# H14R90.net
KiCad netlist of a schematic drawn in EAGLE
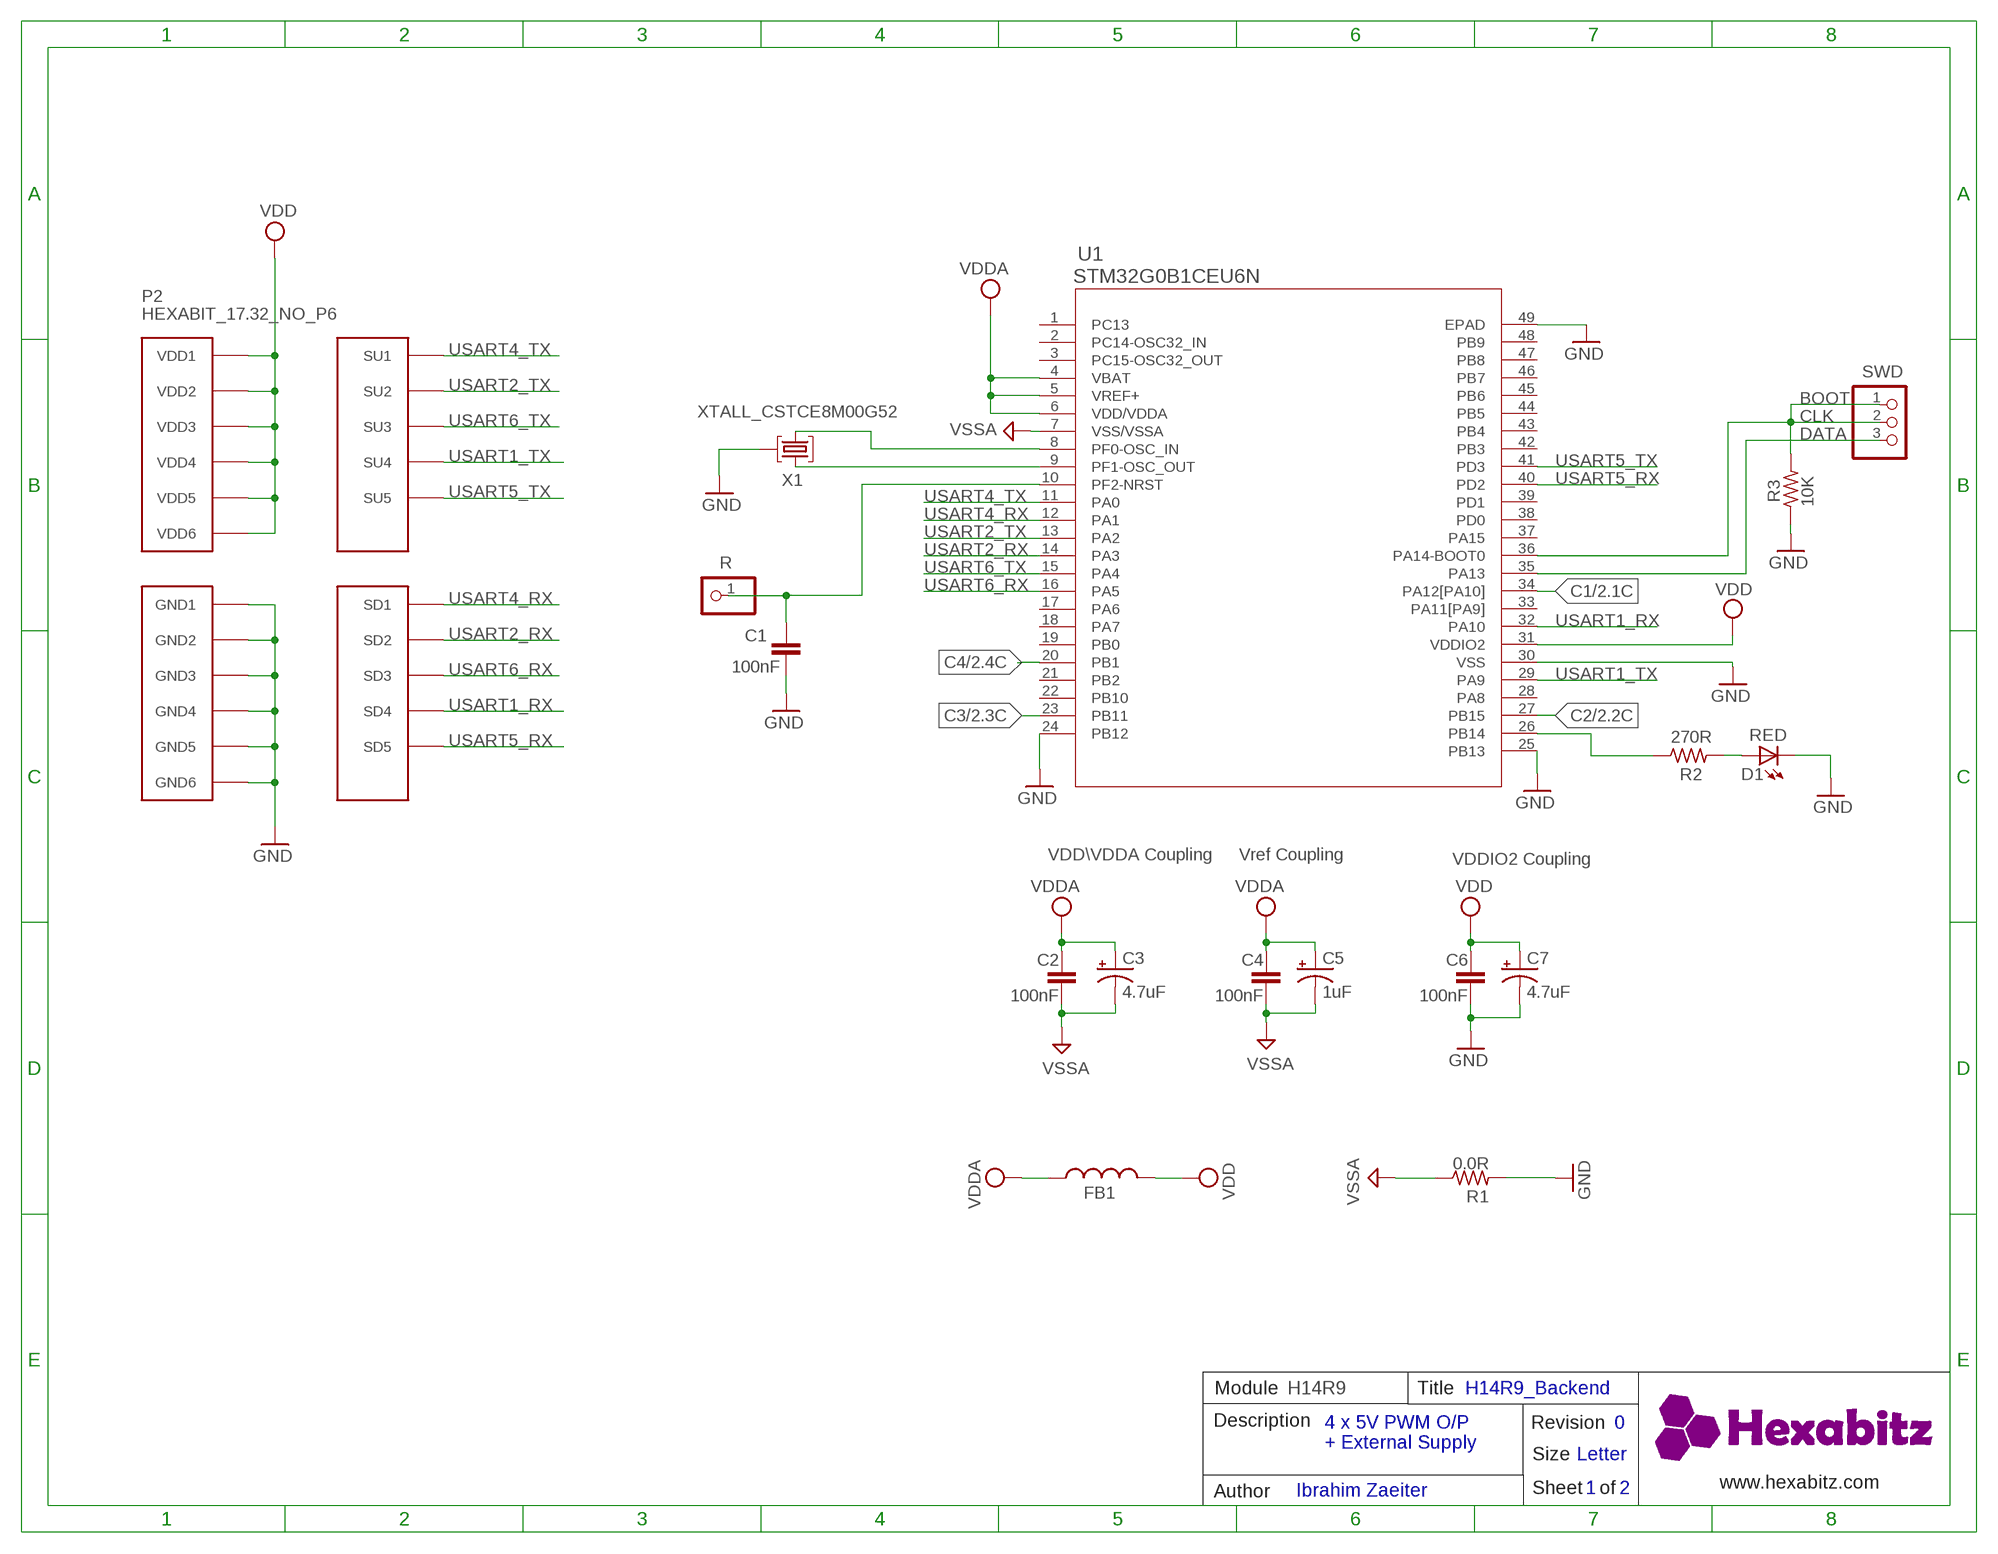
[diagram p0: schematic, sheet 1]
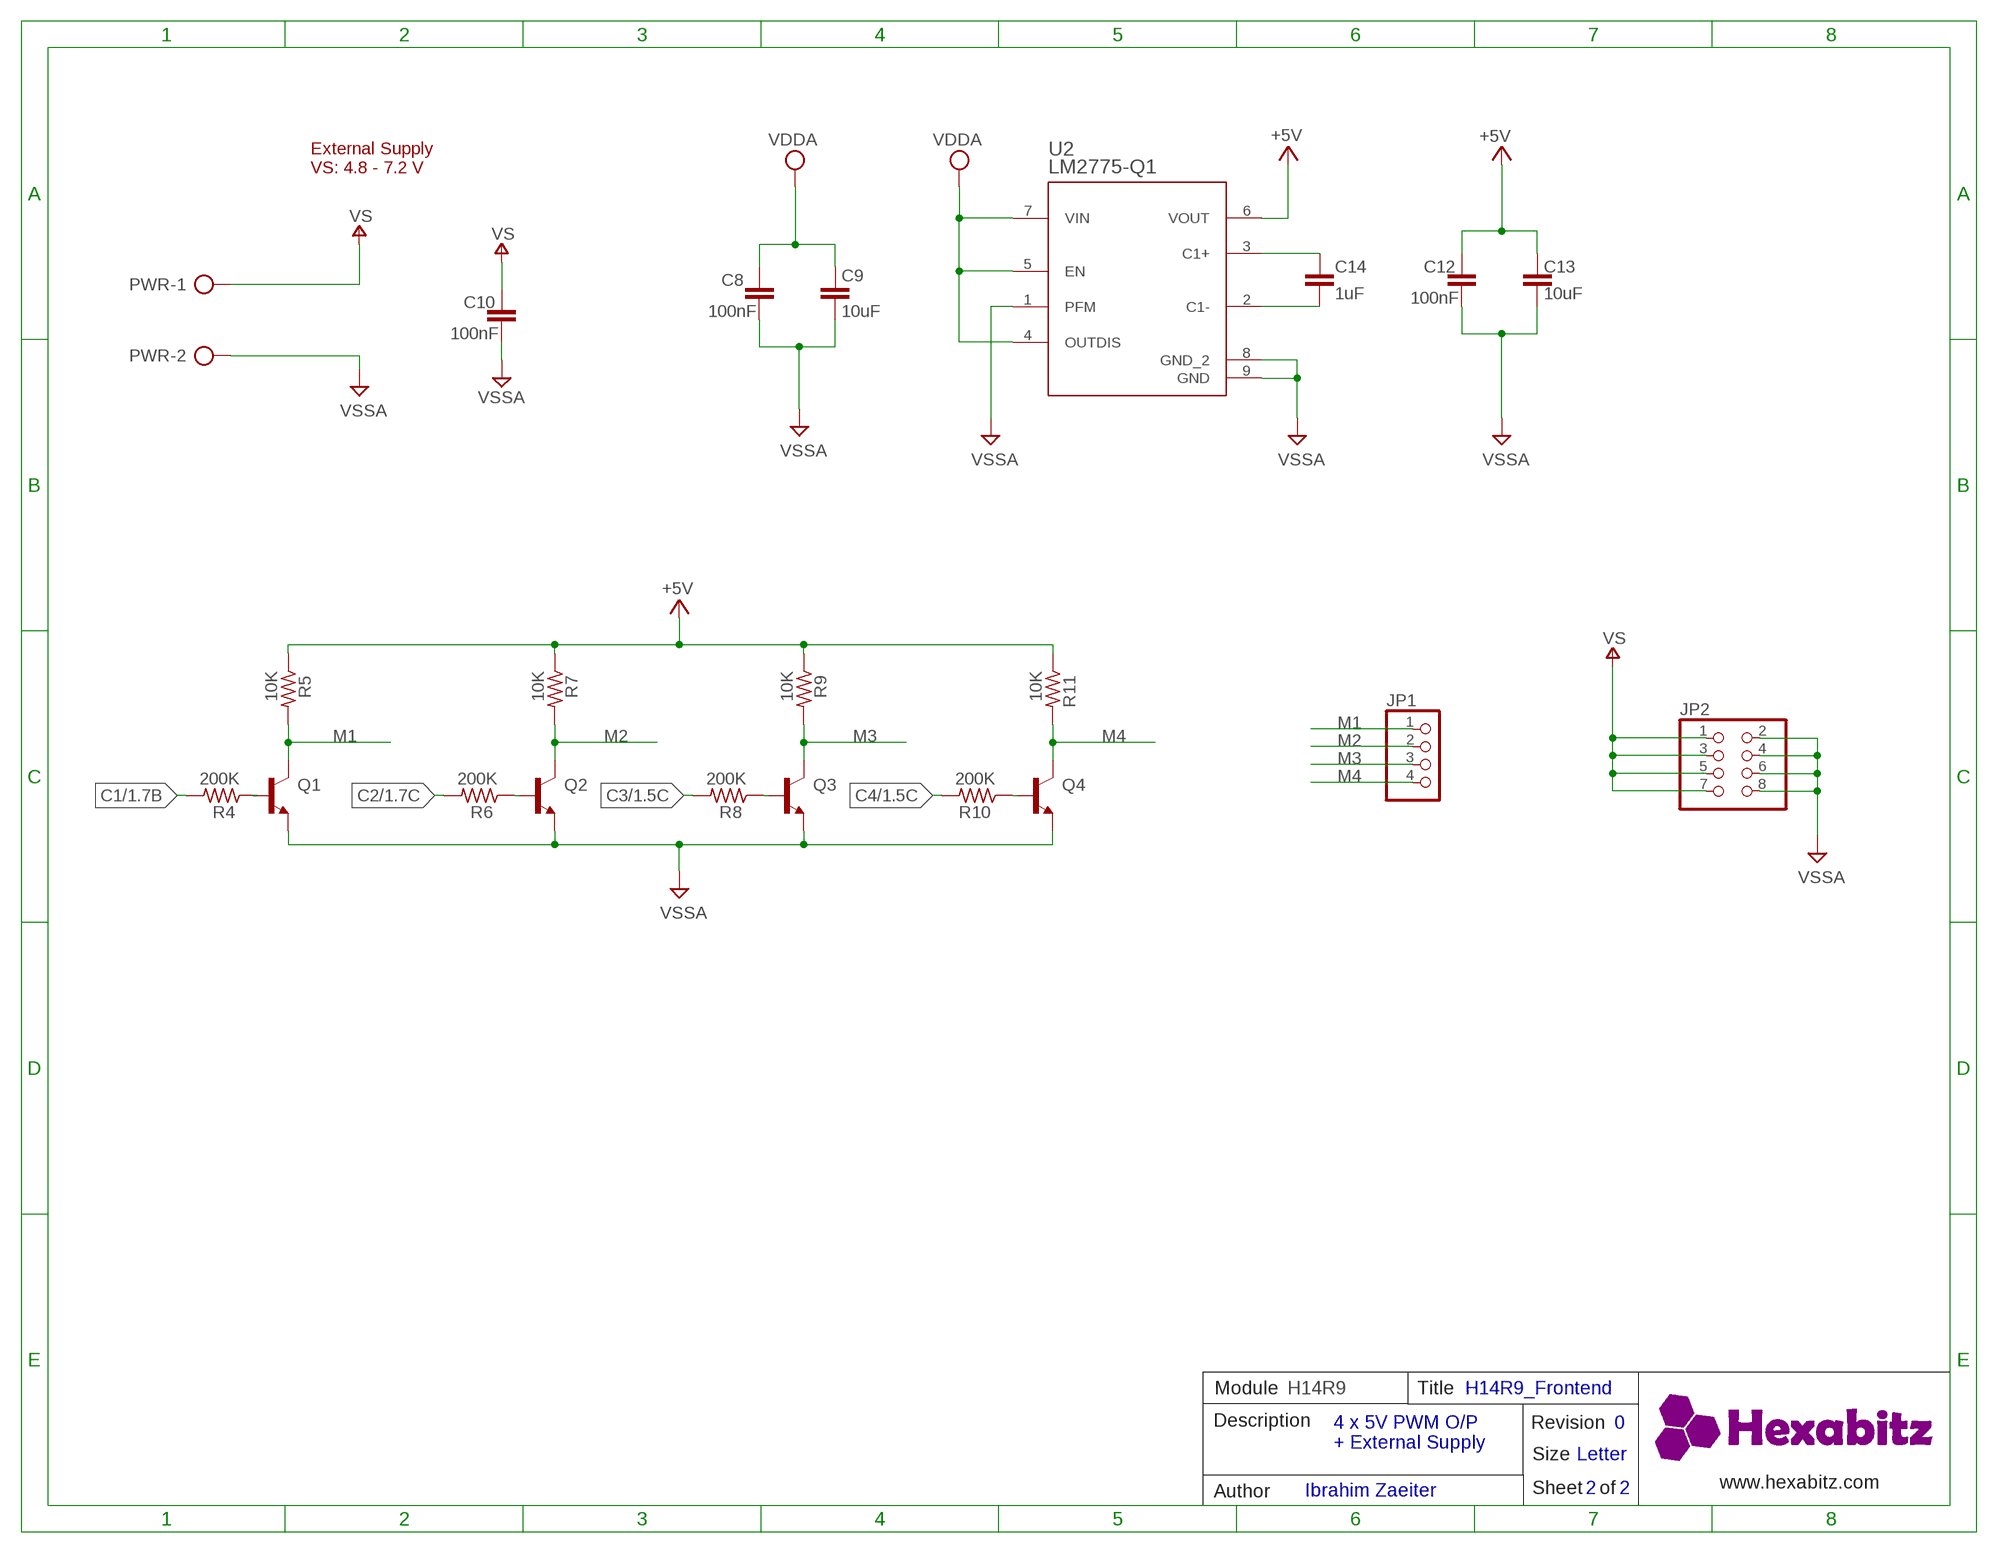
[diagram p1: schematic, sheet 2]

(export (version "E")
  (design (tool "Eeschema 10.0.6"))
  (components
    (comp (ref "C8")
      (value "100nF")
      (footprint "eagle-import:C-0603")
      (libsource (lib "eagle-import") (part "C-0603"))
    )
    (comp (ref "C9")
      (value "10uF")
      (footprint "eagle-import:C-0603")
      (libsource (lib "eagle-import") (part "C-0603"))
    )
    (comp (ref "C10")
      (value "100nF")
      (footprint "eagle-import:C-0603")
      (libsource (lib "eagle-import") (part "C-0603"))
    )
    (comp (ref "C12")
      (value "100nF")
      (footprint "eagle-import:C-0603")
      (libsource (lib "eagle-import") (part "C-0603"))
    )
    (comp (ref "C13")
      (value "10uF")
      (footprint "eagle-import:C-0603")
      (libsource (lib "eagle-import") (part "C-0603"))
    )
    (comp (ref "C14")
      (value "1uF")
      (footprint "eagle-import:C-0603")
      (libsource (lib "eagle-import") (part "C-0603"))
    )
    (comp (ref "JP1")
      (value "PINHD-1X4")
      (footprint "eagle-import:1X04")
      (libsource (lib "eagle-import") (part "PINHD-1X4"))
    )
    (comp (ref "JP2")
      (value "PINHD-2X4")
      (footprint "eagle-import:2X04")
      (libsource (lib "eagle-import") (part "PINHD-2X4"))
    )
    (comp (ref "PWR")
      (value "AK500/2")
      (footprint "eagle-import:AK500_2")
      (libsource (lib "eagle-import") (part "AK500/2"))
    )
    (comp (ref "Q1")
      (value "MMBT3904LT1")
      (footprint "eagle-import:MMBT3904LT1")
      (libsource (lib "eagle-import") (part "MMBT3904LT1"))
    )
    (comp (ref "Q2")
      (value "MMBT3904LT1")
      (footprint "eagle-import:MMBT3904LT1")
      (libsource (lib "eagle-import") (part "MMBT3904LT1"))
    )
    (comp (ref "Q3")
      (value "MMBT3904LT1")
      (footprint "eagle-import:MMBT3904LT1")
      (libsource (lib "eagle-import") (part "MMBT3904LT1"))
    )
    (comp (ref "Q4")
      (value "MMBT3904LT1")
      (footprint "eagle-import:MMBT3904LT1")
      (libsource (lib "eagle-import") (part "MMBT3904LT1"))
    )
    (comp (ref "R4")
      (value "200K")
      (footprint "eagle-import:R-0603")
      (libsource (lib "eagle-import") (part "R-0603"))
    )
    (comp (ref "R5")
      (value "10K")
      (footprint "eagle-import:R-0603")
      (libsource (lib "eagle-import") (part "R-0603"))
    )
    (comp (ref "R6")
      (value "200K")
      (footprint "eagle-import:R-0603")
      (libsource (lib "eagle-import") (part "R-0603"))
    )
    (comp (ref "R7")
      (value "10K")
      (footprint "eagle-import:R-0603")
      (libsource (lib "eagle-import") (part "R-0603"))
    )
    (comp (ref "R8")
      (value "200K")
      (footprint "eagle-import:R-0603")
      (libsource (lib "eagle-import") (part "R-0603"))
    )
    (comp (ref "R9")
      (value "10K")
      (footprint "eagle-import:R-0603")
      (libsource (lib "eagle-import") (part "R-0603"))
    )
    (comp (ref "R10")
      (value "200K")
      (footprint "eagle-import:R-0603")
      (libsource (lib "eagle-import") (part "R-0603"))
    )
    (comp (ref "R11")
      (value "10K")
      (footprint "eagle-import:R-0603")
      (libsource (lib "eagle-import") (part "R-0603"))
    )
    (comp (ref "U2")
      (value "LM2775-Q1")
      (footprint "eagle-import:DSG0008A")
      (fields (field (name "MANUFACTURER") "Texas Instruments") (field (name "MPN") "LM2775QDSGRQ1"))
      (libsource (lib "eagle-import") (part "LM2775QDSGRQ1"))
    )
    (comp (ref "C1")
      (value "100nF")
      (footprint "eagle-import:C-0603")
      (libsource (lib "eagle-import") (part "C-0603"))
    )
    (comp (ref "C2")
      (value "100nF")
      (footprint "eagle-import:C-0603")
      (libsource (lib "eagle-import") (part "C-0603"))
    )
    (comp (ref "C3")
      (value "4.7uF")
      (footprint "eagle-import:C-0805-POL")
      (libsource (lib "eagle-import") (part "C-0805-POL"))
    )
    (comp (ref "C4")
      (value "100nF")
      (footprint "eagle-import:C-0603")
      (libsource (lib "eagle-import") (part "C-0603"))
    )
    (comp (ref "C5")
      (value "1uF")
      (footprint "eagle-import:C-0805-POL")
      (libsource (lib "eagle-import") (part "C-0805-POL"))
    )
    (comp (ref "C6")
      (value "100nF")
      (footprint "eagle-import:C-0603")
      (libsource (lib "eagle-import") (part "C-0603"))
    )
    (comp (ref "C7")
      (value "4.7uF")
      (footprint "eagle-import:C-0805-POL")
      (libsource (lib "eagle-import") (part "C-0805-POL"))
    )
    (comp (ref "D1")
      (value "RED")
      (footprint "eagle-import:VLMS1300-GS08")
      (fields
        (field (name "MPN") "VLMS1300-GS08")
        (field (name "MFN") "Vishay")
        (field (name "MPN_1") "VLMS1300-GS08")
        (field (name "OCTOPART_URL") "https://octopart.com/vlms1300-gs08-vishay-21709201?r=sp&s=_gcP4_q8T1SC6PJQPTQ9yA")
      )
      (libsource (lib "eagle-import") (part "VLMS1300-GS08"))
    )
    (comp (ref "FB1")
      (value "FB-0603")
      (footprint "eagle-import:FB-0603")
      (libsource (lib "eagle-import") (part "FB-0603"))
    )
    (comp (ref "P2")
      (value "HEXABIT_17.32_NO_P6")
      (footprint "eagle-import:HEXABIT_17.32_NO_P6")
      (libsource (lib "eagle-import") (part "HEXABIT_?_NO_P617.32"))
    )
    (comp (ref "R")
      (value "R")
      (footprint "eagle-import:1X01")
      (fields (field (name "MPN") "87227-1"))
      (libsource (lib "eagle-import") (part "PINHD-1X1"))
    )
    (comp (ref "R1")
      (value "0.0R")
      (footprint "eagle-import:R-0603")
      (libsource (lib "eagle-import") (part "R-0603"))
    )
    (comp (ref "R2")
      (value "270R")
      (footprint "eagle-import:R-0603")
      (libsource (lib "eagle-import") (part "R-0603"))
    )
    (comp (ref "R3")
      (value "10K")
      (footprint "eagle-import:R-0603")
      (libsource (lib "eagle-import") (part "R-0603"))
    )
    (comp (ref "SWD")
      (value "PINHD-1X3")
      (footprint "eagle-import:1X03")
      (libsource (lib "eagle-import") (part "PINHD-1X3"))
    )
    (comp (ref "U1")
      (value "STM32G0B1CEU6N")
      (footprint "eagle-import:HEXABITZ_ICS_QFN_B1CEU6_STM-L")
      (libsource (lib "eagle-import") (part "STM32G0B1CEU6N"))
    )
    (comp (ref "X1")
      (value "XTALL_CSTCE8M00G52")
      (footprint "eagle-import:XTALL_CSTCE8M00G52")
      (fields (field (name "MPN") "CSTCE8M00G52Z-R0"))
      (libsource (lib "eagle-import") (part "XTALL_CSTCE8M00G52"))
    )
  )
  (nets
    (net (code "1") (name "+5V") (class "Default")
      (node (ref "C12") (pin "1") (pinfunction "1_1") (pintype "passive"))
      (node (ref "C13") (pin "1") (pinfunction "1_1") (pintype "passive"))
      (node (ref "R11") (pin "1") (pinfunction "1_1") (pintype "passive"))
      (node (ref "R5") (pin "1") (pinfunction "1_1") (pintype "passive"))
      (node (ref "R7") (pin "1") (pinfunction "1_1") (pintype "passive"))
      (node (ref "R9") (pin "1") (pinfunction "1_1") (pintype "passive"))
      (node (ref "U2") (pin "6") (pinfunction "VOUT_6") (pintype "power_in"))
    )
    (net (code "2") (name "C1") (class "Default")
      (node (ref "R4") (pin "2") (pinfunction "2_2") (pintype "passive"))
      (node (ref "U1") (pin "34") (pinfunction "PA12[PA10]_34") (pintype "bidirectional"))
    )
    (net (code "3") (name "C2") (class "Default")
      (node (ref "R6") (pin "2") (pinfunction "2_2") (pintype "passive"))
      (node (ref "U1") (pin "27") (pinfunction "PB15_27") (pintype "bidirectional"))
    )
    (net (code "4") (name "C3") (class "Default")
      (node (ref "R8") (pin "2") (pinfunction "2_2") (pintype "passive"))
      (node (ref "U1") (pin "23") (pinfunction "PB11_23") (pintype "bidirectional"))
    )
    (net (code "5") (name "C4") (class "Default")
      (node (ref "R10") (pin "2") (pinfunction "2_2") (pintype "passive"))
      (node (ref "U1") (pin "20") (pinfunction "PB1_20") (pintype "bidirectional"))
    )
    (net (code "6") (name "CLK") (class "Default")
      (node (ref "R3") (pin "2") (pinfunction "2_2") (pintype "passive"))
      (node (ref "SWD") (pin "1") (pinfunction "1_1") (pintype "passive"))
      (node (ref "SWD") (pin "2") (pinfunction "2_2") (pintype "passive"))
      (node (ref "U1") (pin "36") (pinfunction "PA14-BOOT0_36") (pintype "bidirectional"))
    )
    (net (code "7") (name "DATA") (class "Default")
      (node (ref "SWD") (pin "3") (pinfunction "3_3") (pintype "passive"))
      (node (ref "U1") (pin "35") (pinfunction "PA13_35") (pintype "bidirectional"))
    )
    (net (code "8") (name "GND") (class "Default")
      (node (ref "C1") (pin "2") (pinfunction "2_2") (pintype "passive"))
      (node (ref "C6") (pin "2") (pinfunction "2_2") (pintype "passive"))
      (node (ref "C7") (pin "2") (pinfunction "-_2") (pintype "passive"))
      (node (ref "D1") (pin "C") (pinfunction "C_C") (pintype "passive"))
      (node (ref "P2") (pin "PAD_PD10") (pinfunction "GND4_PAD_PD10") (pintype "power_in"))
      (node (ref "P2") (pin "PAD_PD11") (pinfunction "GND5_PAD_PD11") (pintype "power_in"))
      (node (ref "P2") (pin "PAD_PD12") (pinfunction "GND6_PAD_PD12") (pintype "power_in"))
      (node (ref "P2") (pin "PAD_PD7") (pinfunction "GND1_PAD_PD7") (pintype "power_in"))
      (node (ref "P2") (pin "PAD_PD8") (pinfunction "GND2_PAD_PD8") (pintype "power_in"))
      (node (ref "P2") (pin "PAD_PD9") (pinfunction "GND3_PAD_PD9") (pintype "power_in"))
      (node (ref "R1") (pin "2") (pinfunction "2_2") (pintype "passive"))
      (node (ref "R3") (pin "1") (pinfunction "1_1") (pintype "passive"))
      (node (ref "U1") (pin "24") (pinfunction "PB12_24") (pintype "bidirectional"))
      (node (ref "U1") (pin "25") (pinfunction "PB13_25") (pintype "bidirectional"))
      (node (ref "U1") (pin "30") (pinfunction "VSS_30") (pintype "passive"))
      (node (ref "U1") (pin "49") (pinfunction "EPAD_49") (pintype "passive"))
      (node (ref "X1") (pin "P$2") (pinfunction "2_P$2") (pintype "passive"))
    )
    (net (code "9") (name "M1") (class "Default")
      (node (ref "JP1") (pin "1") (pinfunction "1_1") (pintype "passive"))
      (node (ref "Q1") (pin "3") (pinfunction "C_3") (pintype "passive"))
      (node (ref "R5") (pin "2") (pinfunction "2_2") (pintype "passive"))
    )
    (net (code "10") (name "M2") (class "Default")
      (node (ref "JP1") (pin "2") (pinfunction "2_2") (pintype "passive"))
      (node (ref "Q2") (pin "3") (pinfunction "C_3") (pintype "passive"))
      (node (ref "R7") (pin "2") (pinfunction "2_2") (pintype "passive"))
    )
    (net (code "11") (name "M3") (class "Default")
      (node (ref "JP1") (pin "3") (pinfunction "3_3") (pintype "passive"))
      (node (ref "Q3") (pin "3") (pinfunction "C_3") (pintype "passive"))
      (node (ref "R9") (pin "2") (pinfunction "2_2") (pintype "passive"))
    )
    (net (code "12") (name "M4") (class "Default")
      (node (ref "JP1") (pin "4") (pinfunction "4_4") (pintype "passive"))
      (node (ref "Q4") (pin "3") (pinfunction "C_3") (pintype "passive"))
      (node (ref "R11") (pin "2") (pinfunction "2_2") (pintype "passive"))
    )
    (net (code "13") (name "Net-(D1-PadA)") (class "Default")
      (node (ref "D1") (pin "A") (pinfunction "A_A") (pintype "passive"))
      (node (ref "R2") (pin "2") (pinfunction "2_2") (pintype "passive"))
    )
    (net (code "14") (name "Net-(Q1-B)") (class "Default")
      (node (ref "Q1") (pin "1") (pinfunction "B_1") (pintype "passive"))
      (node (ref "R4") (pin "1") (pinfunction "1_1") (pintype "passive"))
    )
    (net (code "15") (name "Net-(Q2-B)") (class "Default")
      (node (ref "Q2") (pin "1") (pinfunction "B_1") (pintype "passive"))
      (node (ref "R6") (pin "1") (pinfunction "1_1") (pintype "passive"))
    )
    (net (code "16") (name "Net-(Q3-B)") (class "Default")
      (node (ref "Q3") (pin "1") (pinfunction "B_1") (pintype "passive"))
      (node (ref "R8") (pin "1") (pinfunction "1_1") (pintype "passive"))
    )
    (net (code "17") (name "Net-(Q4-B)") (class "Default")
      (node (ref "Q4") (pin "1") (pinfunction "B_1") (pintype "passive"))
      (node (ref "R10") (pin "1") (pinfunction "1_1") (pintype "passive"))
    )
    (net (code "18") (name "Net-(U1-PB14)") (class "Default")
      (node (ref "R2") (pin "1") (pinfunction "1_1") (pintype "passive"))
      (node (ref "U1") (pin "26") (pinfunction "PB14_26") (pintype "bidirectional"))
    )
    (net (code "19") (name "Net-(U1-PF0-OSC_IN)") (class "Default")
      (node (ref "U1") (pin "8") (pinfunction "PF0-OSC_IN_8") (pintype "bidirectional"))
      (node (ref "X1") (pin "P$3") (pinfunction "3_P$3") (pintype "passive"))
    )
    (net (code "20") (name "Net-(U1-PF1-OSC_OUT)") (class "Default")
      (node (ref "U1") (pin "9") (pinfunction "PF1-OSC_OUT_9") (pintype "bidirectional"))
      (node (ref "X1") (pin "P$1") (pinfunction "1_P$1") (pintype "passive"))
    )
    (net (code "21") (name "Net-(U1-PF2-NRST)") (class "Default")
      (node (ref "C1") (pin "1") (pinfunction "1_1") (pintype "passive"))
      (node (ref "R") (pin "1") (pinfunction "1_1") (pintype "passive"))
      (node (ref "U1") (pin "10") (pinfunction "PF2-NRST_10") (pintype "bidirectional"))
    )
    (net (code "22") (name "Net-(U2-C1+)") (class "Default")
      (node (ref "C14") (pin "1") (pinfunction "1_1") (pintype "passive"))
      (node (ref "U2") (pin "3") (pinfunction "C1+_3") (pintype "power_in"))
    )
    (net (code "23") (name "Net-(U2-C1-)") (class "Default")
      (node (ref "C14") (pin "2") (pinfunction "2_2") (pintype "passive"))
      (node (ref "U2") (pin "2") (pinfunction "C1-_2") (pintype "power_in"))
    )
    (net (code "24") (name "USART1_RX") (class "Default")
      (node (ref "P2") (pin "PAD_PD4") (pinfunction "SD4_PAD_PD4") (pintype "bidirectional"))
      (node (ref "U1") (pin "32") (pinfunction "PA10_32") (pintype "bidirectional"))
    )
    (net (code "25") (name "USART1_TX") (class "Default")
      (node (ref "P2") (pin "PAD_PU4") (pinfunction "SU4_PAD_PU4") (pintype "bidirectional"))
      (node (ref "U1") (pin "29") (pinfunction "PA9_29") (pintype "bidirectional"))
    )
    (net (code "26") (name "USART2_RX") (class "Default")
      (node (ref "P2") (pin "PAD_PD2") (pinfunction "SD2_PAD_PD2") (pintype "bidirectional"))
      (node (ref "U1") (pin "14") (pinfunction "PA3_14") (pintype "bidirectional"))
    )
    (net (code "27") (name "USART2_TX") (class "Default")
      (node (ref "P2") (pin "PAD_PU2") (pinfunction "SU2_PAD_PU2") (pintype "bidirectional"))
      (node (ref "U1") (pin "13") (pinfunction "PA2_13") (pintype "bidirectional"))
    )
    (net (code "28") (name "USART4_RX") (class "Default")
      (node (ref "P2") (pin "PAD_PD1") (pinfunction "SD1_PAD_PD1") (pintype "bidirectional"))
      (node (ref "U1") (pin "12") (pinfunction "PA1_12") (pintype "bidirectional"))
    )
    (net (code "29") (name "USART4_TX") (class "Default")
      (node (ref "P2") (pin "PAD_PU1") (pinfunction "SU1_PAD_PU1") (pintype "bidirectional"))
      (node (ref "U1") (pin "11") (pinfunction "PA0_11") (pintype "bidirectional"))
    )
    (net (code "30") (name "USART5_RX") (class "Default")
      (node (ref "P2") (pin "PAD_PD5") (pinfunction "SD5_PAD_PD5") (pintype "bidirectional"))
      (node (ref "U1") (pin "40") (pinfunction "PD2_40") (pintype "bidirectional"))
    )
    (net (code "31") (name "USART5_TX") (class "Default")
      (node (ref "P2") (pin "PAD_PU5") (pinfunction "SU5_PAD_PU5") (pintype "bidirectional"))
      (node (ref "U1") (pin "41") (pinfunction "PD3_41") (pintype "bidirectional"))
    )
    (net (code "32") (name "USART6_RX") (class "Default")
      (node (ref "P2") (pin "PAD_PD3") (pinfunction "SD3_PAD_PD3") (pintype "bidirectional"))
      (node (ref "U1") (pin "16") (pinfunction "PA5_16") (pintype "bidirectional"))
    )
    (net (code "33") (name "USART6_TX") (class "Default")
      (node (ref "P2") (pin "PAD_PU3") (pinfunction "SU3_PAD_PU3") (pintype "bidirectional"))
      (node (ref "U1") (pin "15") (pinfunction "PA4_15") (pintype "bidirectional"))
    )
    (net (code "34") (name "V+") (class "Default")
      (node (ref "C10") (pin "1") (pinfunction "1_1") (pintype "passive"))
      (node (ref "JP2") (pin "1") (pinfunction "1_1") (pintype "passive"))
      (node (ref "JP2") (pin "3") (pinfunction "3_3") (pintype "passive"))
      (node (ref "JP2") (pin "5") (pinfunction "5_5") (pintype "passive"))
      (node (ref "JP2") (pin "7") (pinfunction "7_7") (pintype "passive"))
      (node (ref "PWR") (pin "1") (pinfunction "KL_1") (pintype "passive"))
    )
    (net (code "35") (name "VDD") (class "Default")
      (node (ref "C6") (pin "1") (pinfunction "1_1") (pintype "passive"))
      (node (ref "C7") (pin "1") (pinfunction "+_1") (pintype "passive"))
      (node (ref "FB1") (pin "2") (pinfunction "2_2") (pintype "passive"))
      (node (ref "P2") (pin "PAD_PU10") (pinfunction "VDD4_PAD_PU10") (pintype "power_in"))
      (node (ref "P2") (pin "PAD_PU11") (pinfunction "VDD5_PAD_PU11") (pintype "power_in"))
      (node (ref "P2") (pin "PAD_PU12") (pinfunction "VDD6_PAD_PU12") (pintype "power_in"))
      (node (ref "P2") (pin "PAD_PU7") (pinfunction "VDD1_PAD_PU7") (pintype "power_in"))
      (node (ref "P2") (pin "PAD_PU8") (pinfunction "VDD2_PAD_PU8") (pintype "power_in"))
      (node (ref "P2") (pin "PAD_PU9") (pinfunction "VDD3_PAD_PU9") (pintype "power_in"))
      (node (ref "U1") (pin "31") (pinfunction "VDDIO2_31") (pintype "power_in"))
    )
    (net (code "36") (name "VDDA") (class "Default")
      (node (ref "C2") (pin "1") (pinfunction "1_1") (pintype "passive"))
      (node (ref "C3") (pin "1") (pinfunction "+_1") (pintype "passive"))
      (node (ref "C4") (pin "1") (pinfunction "1_1") (pintype "passive"))
      (node (ref "C5") (pin "1") (pinfunction "+_1") (pintype "passive"))
      (node (ref "C8") (pin "1") (pinfunction "1_1") (pintype "passive"))
      (node (ref "C9") (pin "1") (pinfunction "1_1") (pintype "passive"))
      (node (ref "FB1") (pin "1") (pinfunction "1_1") (pintype "passive"))
      (node (ref "U1") (pin "4") (pinfunction "VBAT_4") (pintype "power_in"))
      (node (ref "U1") (pin "5") (pinfunction "VREF+_5") (pintype "power_in"))
      (node (ref "U1") (pin "6") (pinfunction "VDD/VDDA_6") (pintype "power_in"))
      (node (ref "U2") (pin "4") (pinfunction "OUTDIS_4") (pintype "input"))
      (node (ref "U2") (pin "5") (pinfunction "EN_5") (pintype "input"))
      (node (ref "U2") (pin "7") (pinfunction "VIN_7") (pintype "power_in"))
    )
    (net (code "37") (name "VSSA") (class "Default")
      (node (ref "C10") (pin "2") (pinfunction "2_2") (pintype "passive"))
      (node (ref "C12") (pin "2") (pinfunction "2_2") (pintype "passive"))
      (node (ref "C13") (pin "2") (pinfunction "2_2") (pintype "passive"))
      (node (ref "C2") (pin "2") (pinfunction "2_2") (pintype "passive"))
      (node (ref "C3") (pin "2") (pinfunction "-_2") (pintype "passive"))
      (node (ref "C4") (pin "2") (pinfunction "2_2") (pintype "passive"))
      (node (ref "C5") (pin "2") (pinfunction "-_2") (pintype "passive"))
      (node (ref "C8") (pin "2") (pinfunction "2_2") (pintype "passive"))
      (node (ref "C9") (pin "2") (pinfunction "2_2") (pintype "passive"))
      (node (ref "JP2") (pin "2") (pinfunction "2_2") (pintype "passive"))
      (node (ref "JP2") (pin "4") (pinfunction "4_4") (pintype "passive"))
      (node (ref "JP2") (pin "6") (pinfunction "6_6") (pintype "passive"))
      (node (ref "JP2") (pin "8") (pinfunction "8_8") (pintype "passive"))
      (node (ref "PWR") (pin "2") (pinfunction "KL_2") (pintype "passive"))
      (node (ref "Q1") (pin "2") (pinfunction "E_2") (pintype "passive"))
      (node (ref "Q2") (pin "2") (pinfunction "E_2") (pintype "passive"))
      (node (ref "Q3") (pin "2") (pinfunction "E_2") (pintype "passive"))
      (node (ref "Q4") (pin "2") (pinfunction "E_2") (pintype "passive"))
      (node (ref "R1") (pin "1") (pinfunction "1_1") (pintype "passive"))
      (node (ref "U1") (pin "7") (pinfunction "VSS/VSSA_7") (pintype "passive"))
      (node (ref "U2") (pin "1") (pinfunction "PFM_1") (pintype "input"))
      (node (ref "U2") (pin "8") (pinfunction "GND_2_8") (pintype "power_in"))
      (node (ref "U2") (pin "9") (pinfunction "GND_9") (pintype "power_in"))
    )
    (net (code "38") (name "unconnected-(U1-PA6-Pad17)") (class "Default")
      (node (ref "U1") (pin "17") (pinfunction "PA6_17") (pintype "bidirectional"))
    )
    (net (code "39") (name "unconnected-(U1-PA7-Pad18)") (class "Default")
      (node (ref "U1") (pin "18") (pinfunction "PA7_18") (pintype "bidirectional"))
    )
    (net (code "40") (name "unconnected-(U1-PA8-Pad28)") (class "Default")
      (node (ref "U1") (pin "28") (pinfunction "PA8_28") (pintype "bidirectional"))
    )
    (net (code "41") (name "unconnected-(U1-PA11[PA9]-Pad33)") (class "Default")
      (node (ref "U1") (pin "33") (pinfunction "PA11[PA9]_33") (pintype "bidirectional"))
    )
    (net (code "42") (name "unconnected-(U1-PA15-Pad37)") (class "Default")
      (node (ref "U1") (pin "37") (pinfunction "PA15_37") (pintype "bidirectional"))
    )
    (net (code "43") (name "unconnected-(U1-PB0-Pad19)") (class "Default")
      (node (ref "U1") (pin "19") (pinfunction "PB0_19") (pintype "bidirectional"))
    )
    (net (code "44") (name "unconnected-(U1-PB2-Pad21)") (class "Default")
      (node (ref "U1") (pin "21") (pinfunction "PB2_21") (pintype "bidirectional"))
    )
    (net (code "45") (name "unconnected-(U1-PB3-Pad42)") (class "Default")
      (node (ref "U1") (pin "42") (pinfunction "PB3_42") (pintype "bidirectional"))
    )
    (net (code "46") (name "unconnected-(U1-PB4-Pad43)") (class "Default")
      (node (ref "U1") (pin "43") (pinfunction "PB4_43") (pintype "bidirectional"))
    )
    (net (code "47") (name "unconnected-(U1-PB5-Pad44)") (class "Default")
      (node (ref "U1") (pin "44") (pinfunction "PB5_44") (pintype "bidirectional"))
    )
    (net (code "48") (name "unconnected-(U1-PB6-Pad45)") (class "Default")
      (node (ref "U1") (pin "45") (pinfunction "PB6_45") (pintype "bidirectional"))
    )
    (net (code "49") (name "unconnected-(U1-PB7-Pad46)") (class "Default")
      (node (ref "U1") (pin "46") (pinfunction "PB7_46") (pintype "bidirectional"))
    )
    (net (code "50") (name "unconnected-(U1-PB8-Pad47)") (class "Default")
      (node (ref "U1") (pin "47") (pinfunction "PB8_47") (pintype "bidirectional"))
    )
    (net (code "51") (name "unconnected-(U1-PB9-Pad48)") (class "Default")
      (node (ref "U1") (pin "48") (pinfunction "PB9_48") (pintype "bidirectional"))
    )
    (net (code "52") (name "unconnected-(U1-PB10-Pad22)") (class "Default")
      (node (ref "U1") (pin "22") (pinfunction "PB10_22") (pintype "bidirectional"))
    )
    (net (code "53") (name "unconnected-(U1-PC13-Pad1)") (class "Default")
      (node (ref "U1") (pin "1") (pinfunction "PC13_1") (pintype "bidirectional"))
    )
    (net (code "54") (name "unconnected-(U1-PC14-OSC32_IN-Pad2)") (class "Default")
      (node (ref "U1") (pin "2") (pinfunction "PC14-OSC32_IN_2") (pintype "bidirectional"))
    )
    (net (code "55") (name "unconnected-(U1-PC15-OSC32_OUT-Pad3)") (class "Default")
      (node (ref "U1") (pin "3") (pinfunction "PC15-OSC32_OUT_3") (pintype "bidirectional"))
    )
    (net (code "56") (name "unconnected-(U1-PD0-Pad38)") (class "Default")
      (node (ref "U1") (pin "38") (pinfunction "PD0_38") (pintype "bidirectional"))
    )
    (net (code "57") (name "unconnected-(U1-PD1-Pad39)") (class "Default")
      (node (ref "U1") (pin "39") (pinfunction "PD1_39") (pintype "bidirectional"))
    )
  )
)
